# BOTTOM_pcb_redonda.net
KiCad netlist of a schematic drawn in EAGLE
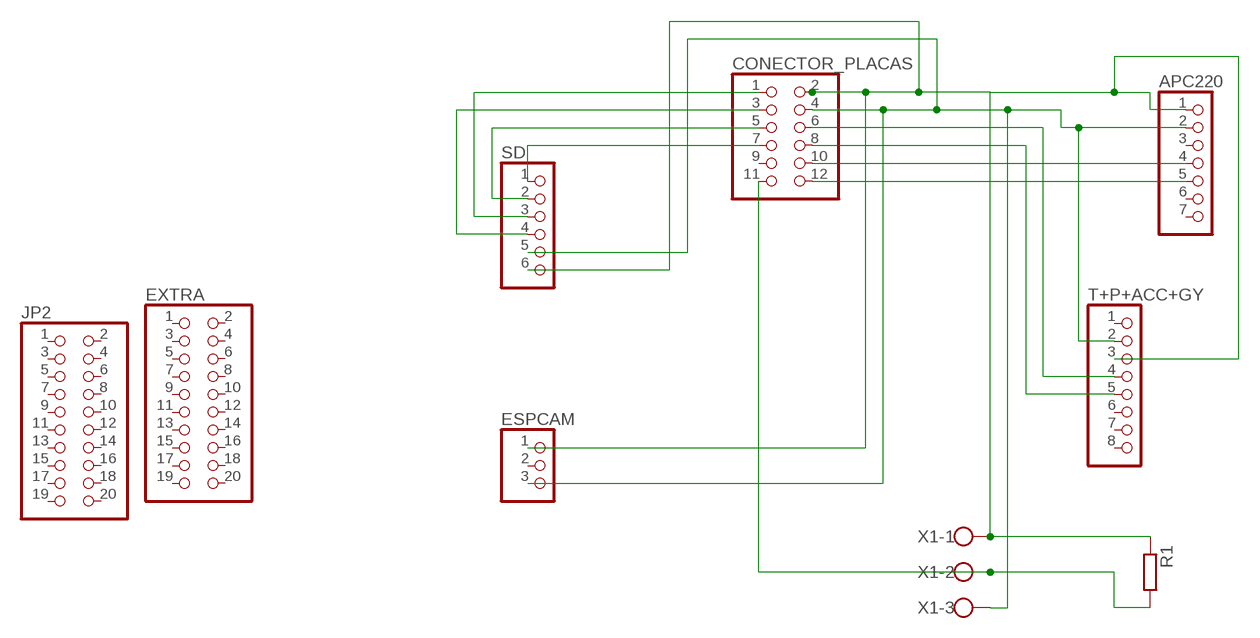
[diagram p0: schematic, sheet 1]

(export (version "E")
  (design (tool "Eeschema 10.0.6"))
  (components
    (comp (ref "APC220")
      (value "PINHD-1X7")
      (footprint "eagle-import:1X07")
      (libsource (lib "eagle-import") (part "PINHD-1X7"))
    )
    (comp (ref "CONECTOR_PLACAS")
      (value "PINHD-2X6")
      (footprint "eagle-import:2X06")
      (libsource (lib "eagle-import") (part "PINHD-2X6"))
    )
    (comp (ref "ESPCAM")
      (value "PINHD-1X3")
      (footprint "eagle-import:1X03")
      (libsource (lib "eagle-import") (part "PINHD-1X3"))
    )
    (comp (ref "EXTRA")
      (value "PINHD-2X10")
      (footprint "eagle-import:2X10")
      (libsource (lib "eagle-import") (part "PINHD-2X10"))
    )
    (comp (ref "JP2")
      (value "PINHD-2X10")
      (footprint "eagle-import:2X10")
      (libsource (lib "eagle-import") (part "PINHD-2X10"))
    )
    (comp (ref "R1")
      (value "R-EU_0207/10")
      (footprint "eagle-import:0207_10")
      (libsource (lib "eagle-import") (part "R-EU_0207/10"))
    )
    (comp (ref "SD")
      (value "PINHD-1X6")
      (footprint "eagle-import:1X06")
      (libsource (lib "eagle-import") (part "PINHD-1X6"))
    )
    (comp (ref "T+P+ACC+GY")
      (value "PINHD-1X8")
      (footprint "eagle-import:1X08")
      (libsource (lib "eagle-import") (part "PINHD-1X8"))
    )
    (comp (ref "X1")
      (value "W237-103")
      (footprint "eagle-import:W237-103")
      (fields (field (name "MPN") "237-103"))
      (libsource (lib "eagle-import") (part "W237-103"))
    )
  )
  (nets
    (net (code "1") (name "Net-(APC220-Pad4)") (class "Default")
      (node (ref "APC220") (pin "4") (pinfunction "4_4") (pintype "passive"))
      (node (ref "CONECTOR_PLACAS") (pin "10") (pinfunction "10_10") (pintype "passive"))
    )
    (net (code "2") (name "Net-(APC220-Pad5)") (class "Default")
      (node (ref "APC220") (pin "5") (pinfunction "5_5") (pintype "passive"))
      (node (ref "CONECTOR_PLACAS") (pin "12") (pinfunction "12_12") (pintype "passive"))
    )
    (net (code "3") (name "Net-(CONECTOR_PLACAS-Pad1)") (class "Default")
      (node (ref "CONECTOR_PLACAS") (pin "1") (pinfunction "1_1") (pintype "passive"))
      (node (ref "SD") (pin "3") (pinfunction "3_3") (pintype "passive"))
    )
    (net (code "4") (name "Net-(CONECTOR_PLACAS-Pad3)") (class "Default")
      (node (ref "CONECTOR_PLACAS") (pin "3") (pinfunction "3_3") (pintype "passive"))
      (node (ref "SD") (pin "4") (pinfunction "4_4") (pintype "passive"))
    )
    (net (code "5") (name "Net-(CONECTOR_PLACAS-Pad5)") (class "Default")
      (node (ref "CONECTOR_PLACAS") (pin "5") (pinfunction "5_5") (pintype "passive"))
      (node (ref "SD") (pin "2") (pinfunction "2_2") (pintype "passive"))
    )
    (net (code "6") (name "Net-(CONECTOR_PLACAS-Pad6)") (class "Default")
      (node (ref "CONECTOR_PLACAS") (pin "6") (pinfunction "6_6") (pintype "passive"))
      (node (ref "T+P+ACC+GY") (pin "4") (pinfunction "4_4") (pintype "passive"))
    )
    (net (code "7") (name "Net-(CONECTOR_PLACAS-Pad7)") (class "Default")
      (node (ref "CONECTOR_PLACAS") (pin "7") (pinfunction "7_7") (pintype "passive"))
      (node (ref "SD") (pin "1") (pinfunction "1_1") (pintype "passive"))
    )
    (net (code "8") (name "Net-(CONECTOR_PLACAS-Pad8)") (class "Default")
      (node (ref "CONECTOR_PLACAS") (pin "8") (pinfunction "8_8") (pintype "passive"))
      (node (ref "T+P+ACC+GY") (pin "5") (pinfunction "5_5") (pintype "passive"))
    )
    (net (code "9") (name "Net-(X1A-KL)") (class "Default")
      (node (ref "APC220") (pin "1") (pinfunction "1_1") (pintype "passive"))
      (node (ref "CONECTOR_PLACAS") (pin "2") (pinfunction "2_2") (pintype "passive"))
      (node (ref "ESPCAM") (pin "1") (pinfunction "1_1") (pintype "passive"))
      (node (ref "R1") (pin "1") (pinfunction "1_1") (pintype "passive"))
      (node (ref "SD") (pin "6") (pinfunction "6_6") (pintype "passive"))
      (node (ref "T+P+ACC+GY") (pin "3") (pinfunction "3_3") (pintype "passive"))
      (node (ref "X1") (pin "1") (pinfunction "KL_1") (pintype "passive"))
    )
    (net (code "10") (name "Net-(X1B-KL)") (class "Default")
      (node (ref "CONECTOR_PLACAS") (pin "11") (pinfunction "11_11") (pintype "passive"))
      (node (ref "R1") (pin "2") (pinfunction "2_2") (pintype "passive"))
      (node (ref "X1") (pin "2") (pinfunction "KL_2") (pintype "passive"))
    )
    (net (code "11") (name "Net-(X1C-KL)") (class "Default")
      (node (ref "APC220") (pin "2") (pinfunction "2_2") (pintype "passive"))
      (node (ref "CONECTOR_PLACAS") (pin "4") (pinfunction "4_4") (pintype "passive"))
      (node (ref "ESPCAM") (pin "3") (pinfunction "3_3") (pintype "passive"))
      (node (ref "SD") (pin "5") (pinfunction "5_5") (pintype "passive"))
      (node (ref "T+P+ACC+GY") (pin "2") (pinfunction "2_2") (pintype "passive"))
      (node (ref "X1") (pin "3") (pinfunction "KL_3") (pintype "passive"))
    )
    (net (code "12") (name "unconnected-(APC220-Pad3)") (class "Default")
      (node (ref "APC220") (pin "3") (pinfunction "3_3") (pintype "passive"))
    )
    (net (code "13") (name "unconnected-(APC220-Pad6)") (class "Default")
      (node (ref "APC220") (pin "6") (pinfunction "6_6") (pintype "passive"))
    )
    (net (code "14") (name "unconnected-(APC220-Pad7)") (class "Default")
      (node (ref "APC220") (pin "7") (pinfunction "7_7") (pintype "passive"))
    )
    (net (code "15") (name "unconnected-(CONECTOR_PLACAS-Pad9)") (class "Default")
      (node (ref "CONECTOR_PLACAS") (pin "9") (pinfunction "9_9") (pintype "passive"))
    )
    (net (code "16") (name "unconnected-(ESPCAM-Pad2)") (class "Default")
      (node (ref "ESPCAM") (pin "2") (pinfunction "2_2") (pintype "passive"))
    )
    (net (code "17") (name "unconnected-(EXTRA-Pad1)") (class "Default")
      (node (ref "EXTRA") (pin "1") (pinfunction "1_1") (pintype "passive"))
    )
    (net (code "18") (name "unconnected-(EXTRA-Pad2)") (class "Default")
      (node (ref "EXTRA") (pin "2") (pinfunction "2_2") (pintype "passive"))
    )
    (net (code "19") (name "unconnected-(EXTRA-Pad3)") (class "Default")
      (node (ref "EXTRA") (pin "3") (pinfunction "3_3") (pintype "passive"))
    )
    (net (code "20") (name "unconnected-(EXTRA-Pad4)") (class "Default")
      (node (ref "EXTRA") (pin "4") (pinfunction "4_4") (pintype "passive"))
    )
    (net (code "21") (name "unconnected-(EXTRA-Pad5)") (class "Default")
      (node (ref "EXTRA") (pin "5") (pinfunction "5_5") (pintype "passive"))
    )
    (net (code "22") (name "unconnected-(EXTRA-Pad6)") (class "Default")
      (node (ref "EXTRA") (pin "6") (pinfunction "6_6") (pintype "passive"))
    )
    (net (code "23") (name "unconnected-(EXTRA-Pad7)") (class "Default")
      (node (ref "EXTRA") (pin "7") (pinfunction "7_7") (pintype "passive"))
    )
    (net (code "24") (name "unconnected-(EXTRA-Pad8)") (class "Default")
      (node (ref "EXTRA") (pin "8") (pinfunction "8_8") (pintype "passive"))
    )
    (net (code "25") (name "unconnected-(EXTRA-Pad9)") (class "Default")
      (node (ref "EXTRA") (pin "9") (pinfunction "9_9") (pintype "passive"))
    )
    (net (code "26") (name "unconnected-(EXTRA-Pad10)") (class "Default")
      (node (ref "EXTRA") (pin "10") (pinfunction "10_10") (pintype "passive"))
    )
    (net (code "27") (name "unconnected-(EXTRA-Pad11)") (class "Default")
      (node (ref "EXTRA") (pin "11") (pinfunction "11_11") (pintype "passive"))
    )
    (net (code "28") (name "unconnected-(EXTRA-Pad12)") (class "Default")
      (node (ref "EXTRA") (pin "12") (pinfunction "12_12") (pintype "passive"))
    )
    (net (code "29") (name "unconnected-(EXTRA-Pad13)") (class "Default")
      (node (ref "EXTRA") (pin "13") (pinfunction "13_13") (pintype "passive"))
    )
    (net (code "30") (name "unconnected-(EXTRA-Pad14)") (class "Default")
      (node (ref "EXTRA") (pin "14") (pinfunction "14_14") (pintype "passive"))
    )
    (net (code "31") (name "unconnected-(EXTRA-Pad15)") (class "Default")
      (node (ref "EXTRA") (pin "15") (pinfunction "15_15") (pintype "passive"))
    )
    (net (code "32") (name "unconnected-(EXTRA-Pad16)") (class "Default")
      (node (ref "EXTRA") (pin "16") (pinfunction "16_16") (pintype "passive"))
    )
    (net (code "33") (name "unconnected-(EXTRA-Pad17)") (class "Default")
      (node (ref "EXTRA") (pin "17") (pinfunction "17_17") (pintype "passive"))
    )
    (net (code "34") (name "unconnected-(EXTRA-Pad18)") (class "Default")
      (node (ref "EXTRA") (pin "18") (pinfunction "18_18") (pintype "passive"))
    )
    (net (code "35") (name "unconnected-(EXTRA-Pad19)") (class "Default")
      (node (ref "EXTRA") (pin "19") (pinfunction "19_19") (pintype "passive"))
    )
    (net (code "36") (name "unconnected-(EXTRA-Pad20)") (class "Default")
      (node (ref "EXTRA") (pin "20") (pinfunction "20_20") (pintype "passive"))
    )
    (net (code "37") (name "unconnected-(JP2-Pad1)") (class "Default")
      (node (ref "JP2") (pin "1") (pinfunction "1_1") (pintype "passive"))
    )
    (net (code "38") (name "unconnected-(JP2-Pad2)") (class "Default")
      (node (ref "JP2") (pin "2") (pinfunction "2_2") (pintype "passive"))
    )
    (net (code "39") (name "unconnected-(JP2-Pad3)") (class "Default")
      (node (ref "JP2") (pin "3") (pinfunction "3_3") (pintype "passive"))
    )
    (net (code "40") (name "unconnected-(JP2-Pad4)") (class "Default")
      (node (ref "JP2") (pin "4") (pinfunction "4_4") (pintype "passive"))
    )
    (net (code "41") (name "unconnected-(JP2-Pad5)") (class "Default")
      (node (ref "JP2") (pin "5") (pinfunction "5_5") (pintype "passive"))
    )
    (net (code "42") (name "unconnected-(JP2-Pad6)") (class "Default")
      (node (ref "JP2") (pin "6") (pinfunction "6_6") (pintype "passive"))
    )
    (net (code "43") (name "unconnected-(JP2-Pad7)") (class "Default")
      (node (ref "JP2") (pin "7") (pinfunction "7_7") (pintype "passive"))
    )
    (net (code "44") (name "unconnected-(JP2-Pad8)") (class "Default")
      (node (ref "JP2") (pin "8") (pinfunction "8_8") (pintype "passive"))
    )
    (net (code "45") (name "unconnected-(JP2-Pad9)") (class "Default")
      (node (ref "JP2") (pin "9") (pinfunction "9_9") (pintype "passive"))
    )
    (net (code "46") (name "unconnected-(JP2-Pad10)") (class "Default")
      (node (ref "JP2") (pin "10") (pinfunction "10_10") (pintype "passive"))
    )
    (net (code "47") (name "unconnected-(JP2-Pad11)") (class "Default")
      (node (ref "JP2") (pin "11") (pinfunction "11_11") (pintype "passive"))
    )
    (net (code "48") (name "unconnected-(JP2-Pad12)") (class "Default")
      (node (ref "JP2") (pin "12") (pinfunction "12_12") (pintype "passive"))
    )
    (net (code "49") (name "unconnected-(JP2-Pad13)") (class "Default")
      (node (ref "JP2") (pin "13") (pinfunction "13_13") (pintype "passive"))
    )
    (net (code "50") (name "unconnected-(JP2-Pad14)") (class "Default")
      (node (ref "JP2") (pin "14") (pinfunction "14_14") (pintype "passive"))
    )
    (net (code "51") (name "unconnected-(JP2-Pad15)") (class "Default")
      (node (ref "JP2") (pin "15") (pinfunction "15_15") (pintype "passive"))
    )
    (net (code "52") (name "unconnected-(JP2-Pad16)") (class "Default")
      (node (ref "JP2") (pin "16") (pinfunction "16_16") (pintype "passive"))
    )
    (net (code "53") (name "unconnected-(JP2-Pad17)") (class "Default")
      (node (ref "JP2") (pin "17") (pinfunction "17_17") (pintype "passive"))
    )
    (net (code "54") (name "unconnected-(JP2-Pad18)") (class "Default")
      (node (ref "JP2") (pin "18") (pinfunction "18_18") (pintype "passive"))
    )
    (net (code "55") (name "unconnected-(JP2-Pad19)") (class "Default")
      (node (ref "JP2") (pin "19") (pinfunction "19_19") (pintype "passive"))
    )
    (net (code "56") (name "unconnected-(JP2-Pad20)") (class "Default")
      (node (ref "JP2") (pin "20") (pinfunction "20_20") (pintype "passive"))
    )
    (net (code "57") (name "unconnected-(T+P+ACC+GY-Pad1)") (class "Default")
      (node (ref "T+P+ACC+GY") (pin "1") (pinfunction "1_1") (pintype "passive"))
    )
    (net (code "58") (name "unconnected-(T+P+ACC+GY-Pad6)") (class "Default")
      (node (ref "T+P+ACC+GY") (pin "6") (pinfunction "6_6") (pintype "passive"))
    )
    (net (code "59") (name "unconnected-(T+P+ACC+GY-Pad7)") (class "Default")
      (node (ref "T+P+ACC+GY") (pin "7") (pinfunction "7_7") (pintype "passive"))
    )
    (net (code "60") (name "unconnected-(T+P+ACC+GY-Pad8)") (class "Default")
      (node (ref "T+P+ACC+GY") (pin "8") (pinfunction "8_8") (pintype "passive"))
    )
  )
)
